# IMU.net
KiCad netlist of a schematic drawn in EAGLE
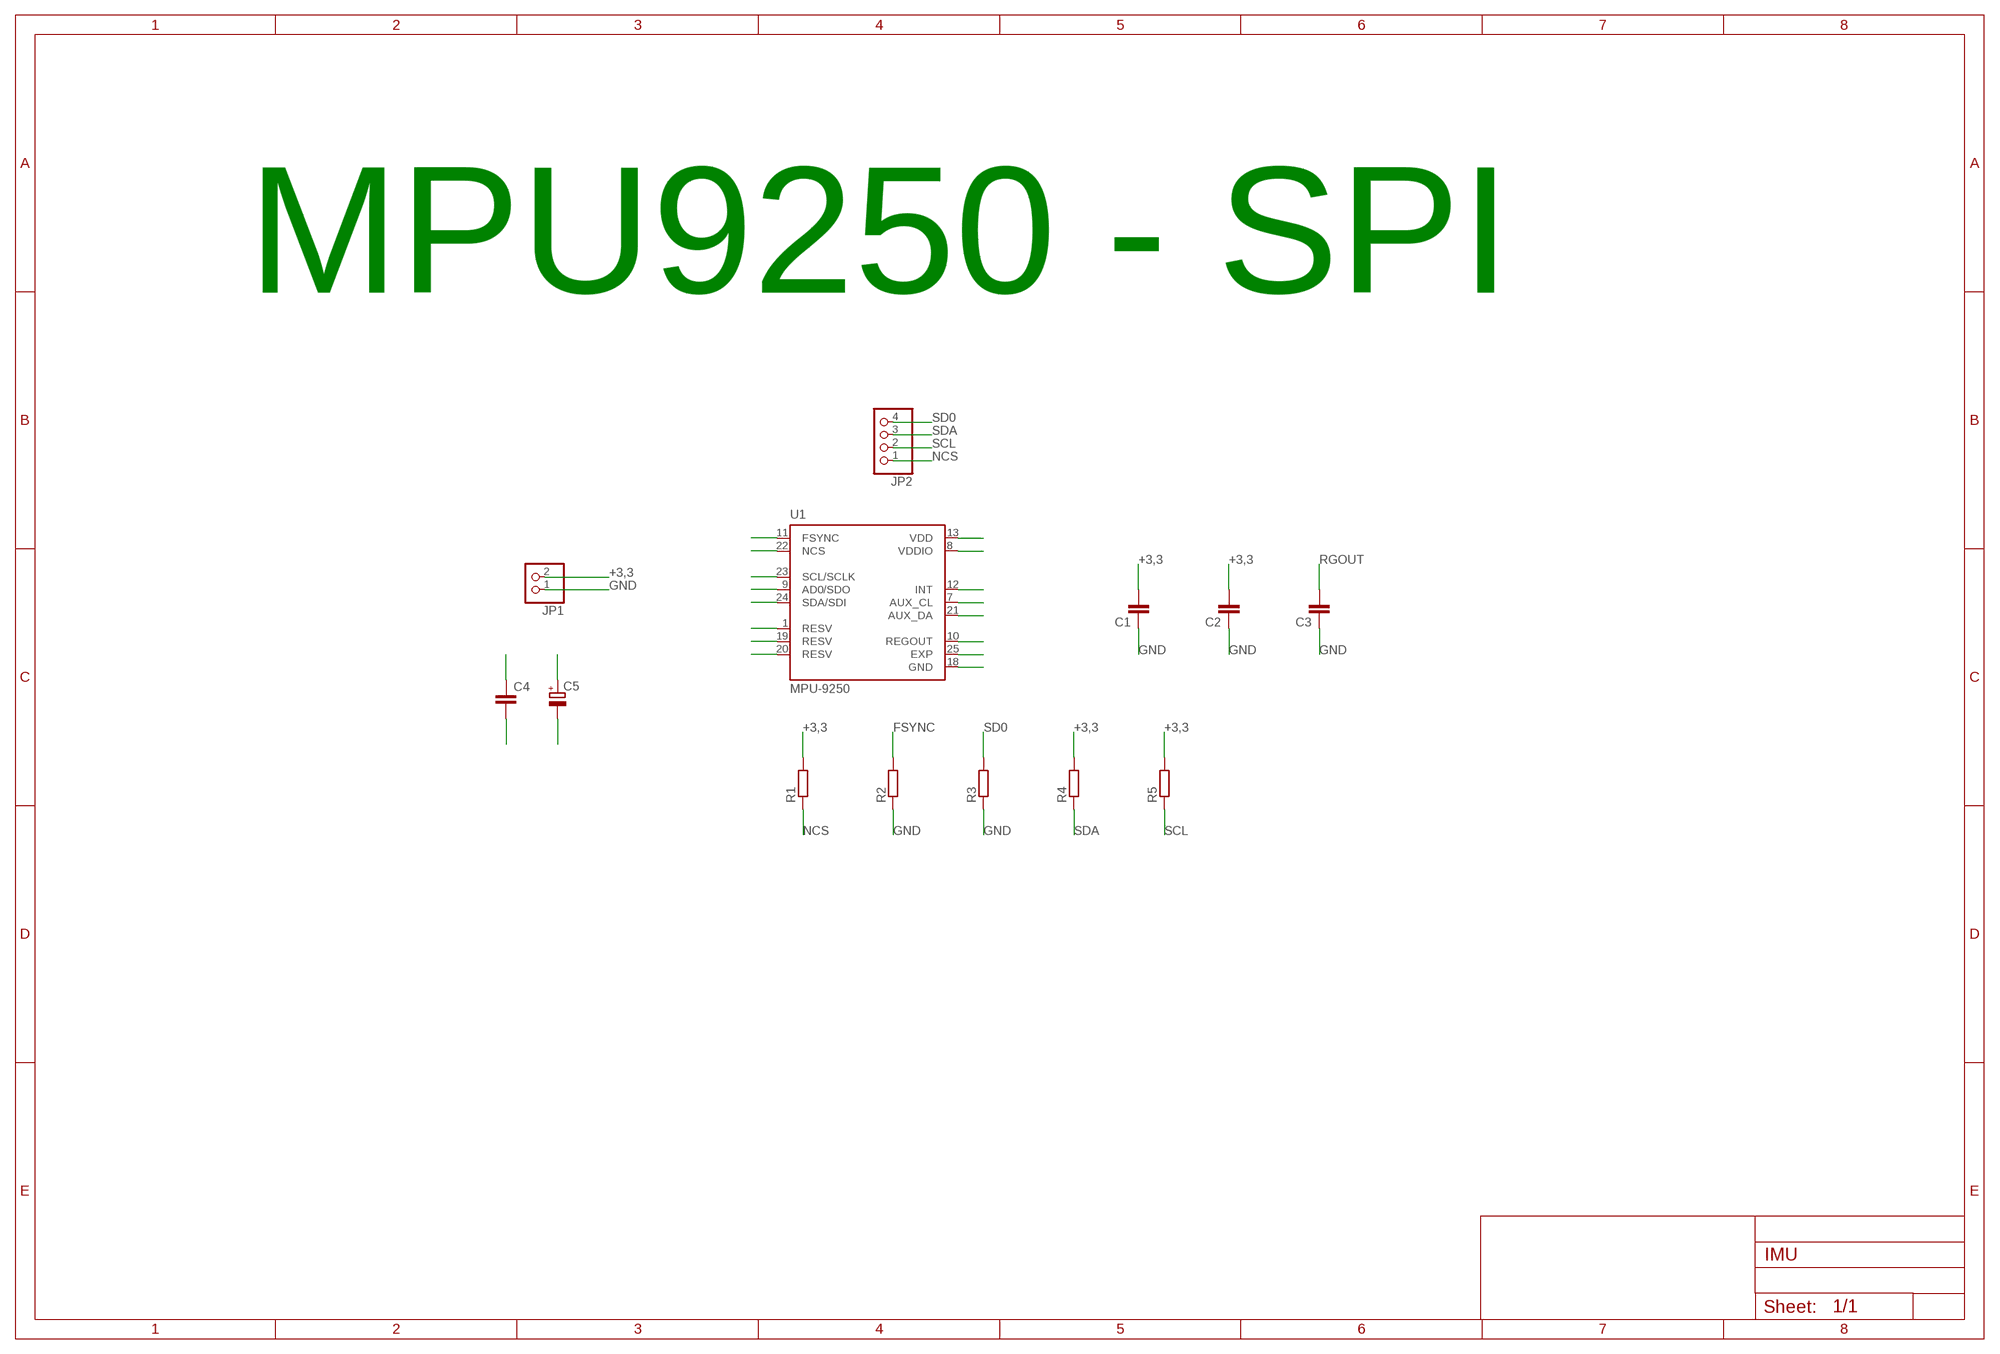
[diagram p0: schematic, sheet 1]

(export (version "E")
  (design (tool "Eeschema 10.0.6"))
  (components
    (comp (ref "C1")
      (value "C-EUC0805")
      (footprint "eagle-import:C0805")
      (libsource (lib "eagle-import") (part "C-EUC0805"))
    )
    (comp (ref "C2")
      (value "C-EUC0805")
      (footprint "eagle-import:C0805")
      (libsource (lib "eagle-import") (part "C-EUC0805"))
    )
    (comp (ref "C3")
      (value "C-EUC0805")
      (footprint "eagle-import:C0805")
      (libsource (lib "eagle-import") (part "C-EUC0805"))
    )
    (comp (ref "C4")
      (value "C-EUC0805")
      (footprint "eagle-import:C0805")
      (libsource (lib "eagle-import") (part "C-EUC0805"))
    )
    (comp (ref "C5")
      (value "CPOL-EUC/6032-28R")
      (footprint "eagle-import:C_6032-28R")
      (libsource (lib "eagle-import") (part "CPOL-EUC/6032-28R"))
    )
    (comp (ref "JP1")
      (value "PINHD-1X2")
      (footprint "eagle-import:1X02")
      (libsource (lib "eagle-import") (part "PINHD-1X2"))
    )
    (comp (ref "JP2")
      (value "PINHD-1X4")
      (footprint "eagle-import:1X04")
      (libsource (lib "eagle-import") (part "PINHD-1X4"))
    )
    (comp (ref "R1")
      (value "R-EU_R0805")
      (footprint "eagle-import:R0805")
      (libsource (lib "eagle-import") (part "R-EU_R0805"))
    )
    (comp (ref "R2")
      (value "R-EU_R0805")
      (footprint "eagle-import:R0805")
      (libsource (lib "eagle-import") (part "R-EU_R0805"))
    )
    (comp (ref "R3")
      (value "R-EU_R0805")
      (footprint "eagle-import:R0805")
      (libsource (lib "eagle-import") (part "R-EU_R0805"))
    )
    (comp (ref "R4")
      (value "R-EU_R0805")
      (footprint "eagle-import:R0805")
      (libsource (lib "eagle-import") (part "R-EU_R0805"))
    )
    (comp (ref "R5")
      (value "R-EU_R0805")
      (footprint "eagle-import:R0805")
      (libsource (lib "eagle-import") (part "R-EU_R0805"))
    )
    (comp (ref "U1")
      (value "MPU-9250")
      (footprint "eagle-import:QFN40P300X300X105-25N")
      (fields (field (name "MF") "InvenSense"))
      (libsource (lib "eagle-import") (part "MPU-9250"))
    )
  )
  (nets
    (net (code "1") (name "/+3,3") (class "Default")
      (node (ref "C1") (pin "2") (pinfunction "2_2") (pintype "passive"))
      (node (ref "C2") (pin "2") (pinfunction "2_2") (pintype "passive"))
      (node (ref "C4") (pin "1") (pinfunction "1_1") (pintype "passive"))
      (node (ref "C5") (pin "+") (pinfunction "+_+") (pintype "passive"))
      (node (ref "JP1") (pin "2") (pinfunction "2_2") (pintype "passive"))
      (node (ref "R1") (pin "2") (pinfunction "2_2") (pintype "passive"))
      (node (ref "R4") (pin "2") (pinfunction "2_2") (pintype "passive"))
      (node (ref "R5") (pin "2") (pinfunction "2_2") (pintype "passive"))
      (node (ref "U1") (pin "1") (pinfunction "RESV_1") (pintype "power_in"))
      (node (ref "U1") (pin "13") (pinfunction "VDD_13") (pintype "power_in"))
      (node (ref "U1") (pin "8") (pinfunction "VDDIO_8") (pintype "power_in"))
    )
    (net (code "2") (name "/FSYNC") (class "Default")
      (node (ref "R2") (pin "2") (pinfunction "2_2") (pintype "passive"))
      (node (ref "U1") (pin "11") (pinfunction "FSYNC_11") (pintype "input"))
    )
    (net (code "3") (name "/GND") (class "Default")
      (node (ref "C1") (pin "1") (pinfunction "1_1") (pintype "passive"))
      (node (ref "C2") (pin "1") (pinfunction "1_1") (pintype "passive"))
      (node (ref "C3") (pin "1") (pinfunction "1_1") (pintype "passive"))
      (node (ref "C4") (pin "2") (pinfunction "2_2") (pintype "passive"))
      (node (ref "C5") (pin "-") (pinfunction "-_-") (pintype "passive"))
      (node (ref "JP1") (pin "1") (pinfunction "1_1") (pintype "passive"))
      (node (ref "R2") (pin "1") (pinfunction "1_1") (pintype "passive"))
      (node (ref "R3") (pin "1") (pinfunction "1_1") (pintype "passive"))
      (node (ref "U1") (pin "18") (pinfunction "GND_18") (pintype "power_in"))
      (node (ref "U1") (pin "20") (pinfunction "RESV_20") (pintype "power_in"))
    )
    (net (code "4") (name "/NCS") (class "Default")
      (node (ref "JP2") (pin "1") (pinfunction "1_1") (pintype "passive"))
      (node (ref "R1") (pin "1") (pinfunction "1_1") (pintype "passive"))
      (node (ref "U1") (pin "22") (pinfunction "NCS_22") (pintype "input"))
    )
    (net (code "5") (name "/RGOUT") (class "Default")
      (node (ref "C3") (pin "2") (pinfunction "2_2") (pintype "passive"))
      (node (ref "U1") (pin "10") (pinfunction "REGOUT_10") (pintype "passive"))
    )
    (net (code "6") (name "/SCL") (class "Default")
      (node (ref "JP2") (pin "2") (pinfunction "2_2") (pintype "passive"))
      (node (ref "R5") (pin "1") (pinfunction "1_1") (pintype "passive"))
      (node (ref "U1") (pin "23") (pinfunction "SCL/SCLK_23") (pintype "input"))
    )
    (net (code "7") (name "/SD0") (class "Default")
      (node (ref "JP2") (pin "4") (pinfunction "4_4") (pintype "passive"))
      (node (ref "R3") (pin "2") (pinfunction "2_2") (pintype "passive"))
      (node (ref "U1") (pin "9") (pinfunction "AD0/SDO_9") (pintype "bidirectional"))
    )
    (net (code "8") (name "/SDA") (class "Default")
      (node (ref "JP2") (pin "3") (pinfunction "3_3") (pintype "passive"))
      (node (ref "R4") (pin "1") (pinfunction "1_1") (pintype "passive"))
      (node (ref "U1") (pin "24") (pinfunction "SDA/SDI_24") (pintype "bidirectional"))
    )
    (net (code "9") (name "unconnected-(U1-AUX_CL-Pad7)") (class "Default")
      (node (ref "U1") (pin "7") (pinfunction "AUX_CL_7") (pintype "output"))
    )
    (net (code "10") (name "unconnected-(U1-AUX_DA-Pad21)") (class "Default")
      (node (ref "U1") (pin "21") (pinfunction "AUX_DA_21") (pintype "output"))
    )
    (net (code "11") (name "unconnected-(U1-EXP-Pad25)") (class "Default")
      (node (ref "U1") (pin "25") (pinfunction "EXP_25") (pintype "power_in"))
    )
    (net (code "12") (name "unconnected-(U1-INT-Pad12)") (class "Default")
      (node (ref "U1") (pin "12") (pinfunction "INT_12") (pintype "output"))
    )
    (net (code "13") (name "unconnected-(U1-RESV-Pad19)") (class "Default")
      (node (ref "U1") (pin "19") (pinfunction "RESV_19") (pintype "power_in"))
    )
  )
)
